# magnetov1.net
KiCad netlist of a schematic drawn in EAGLE
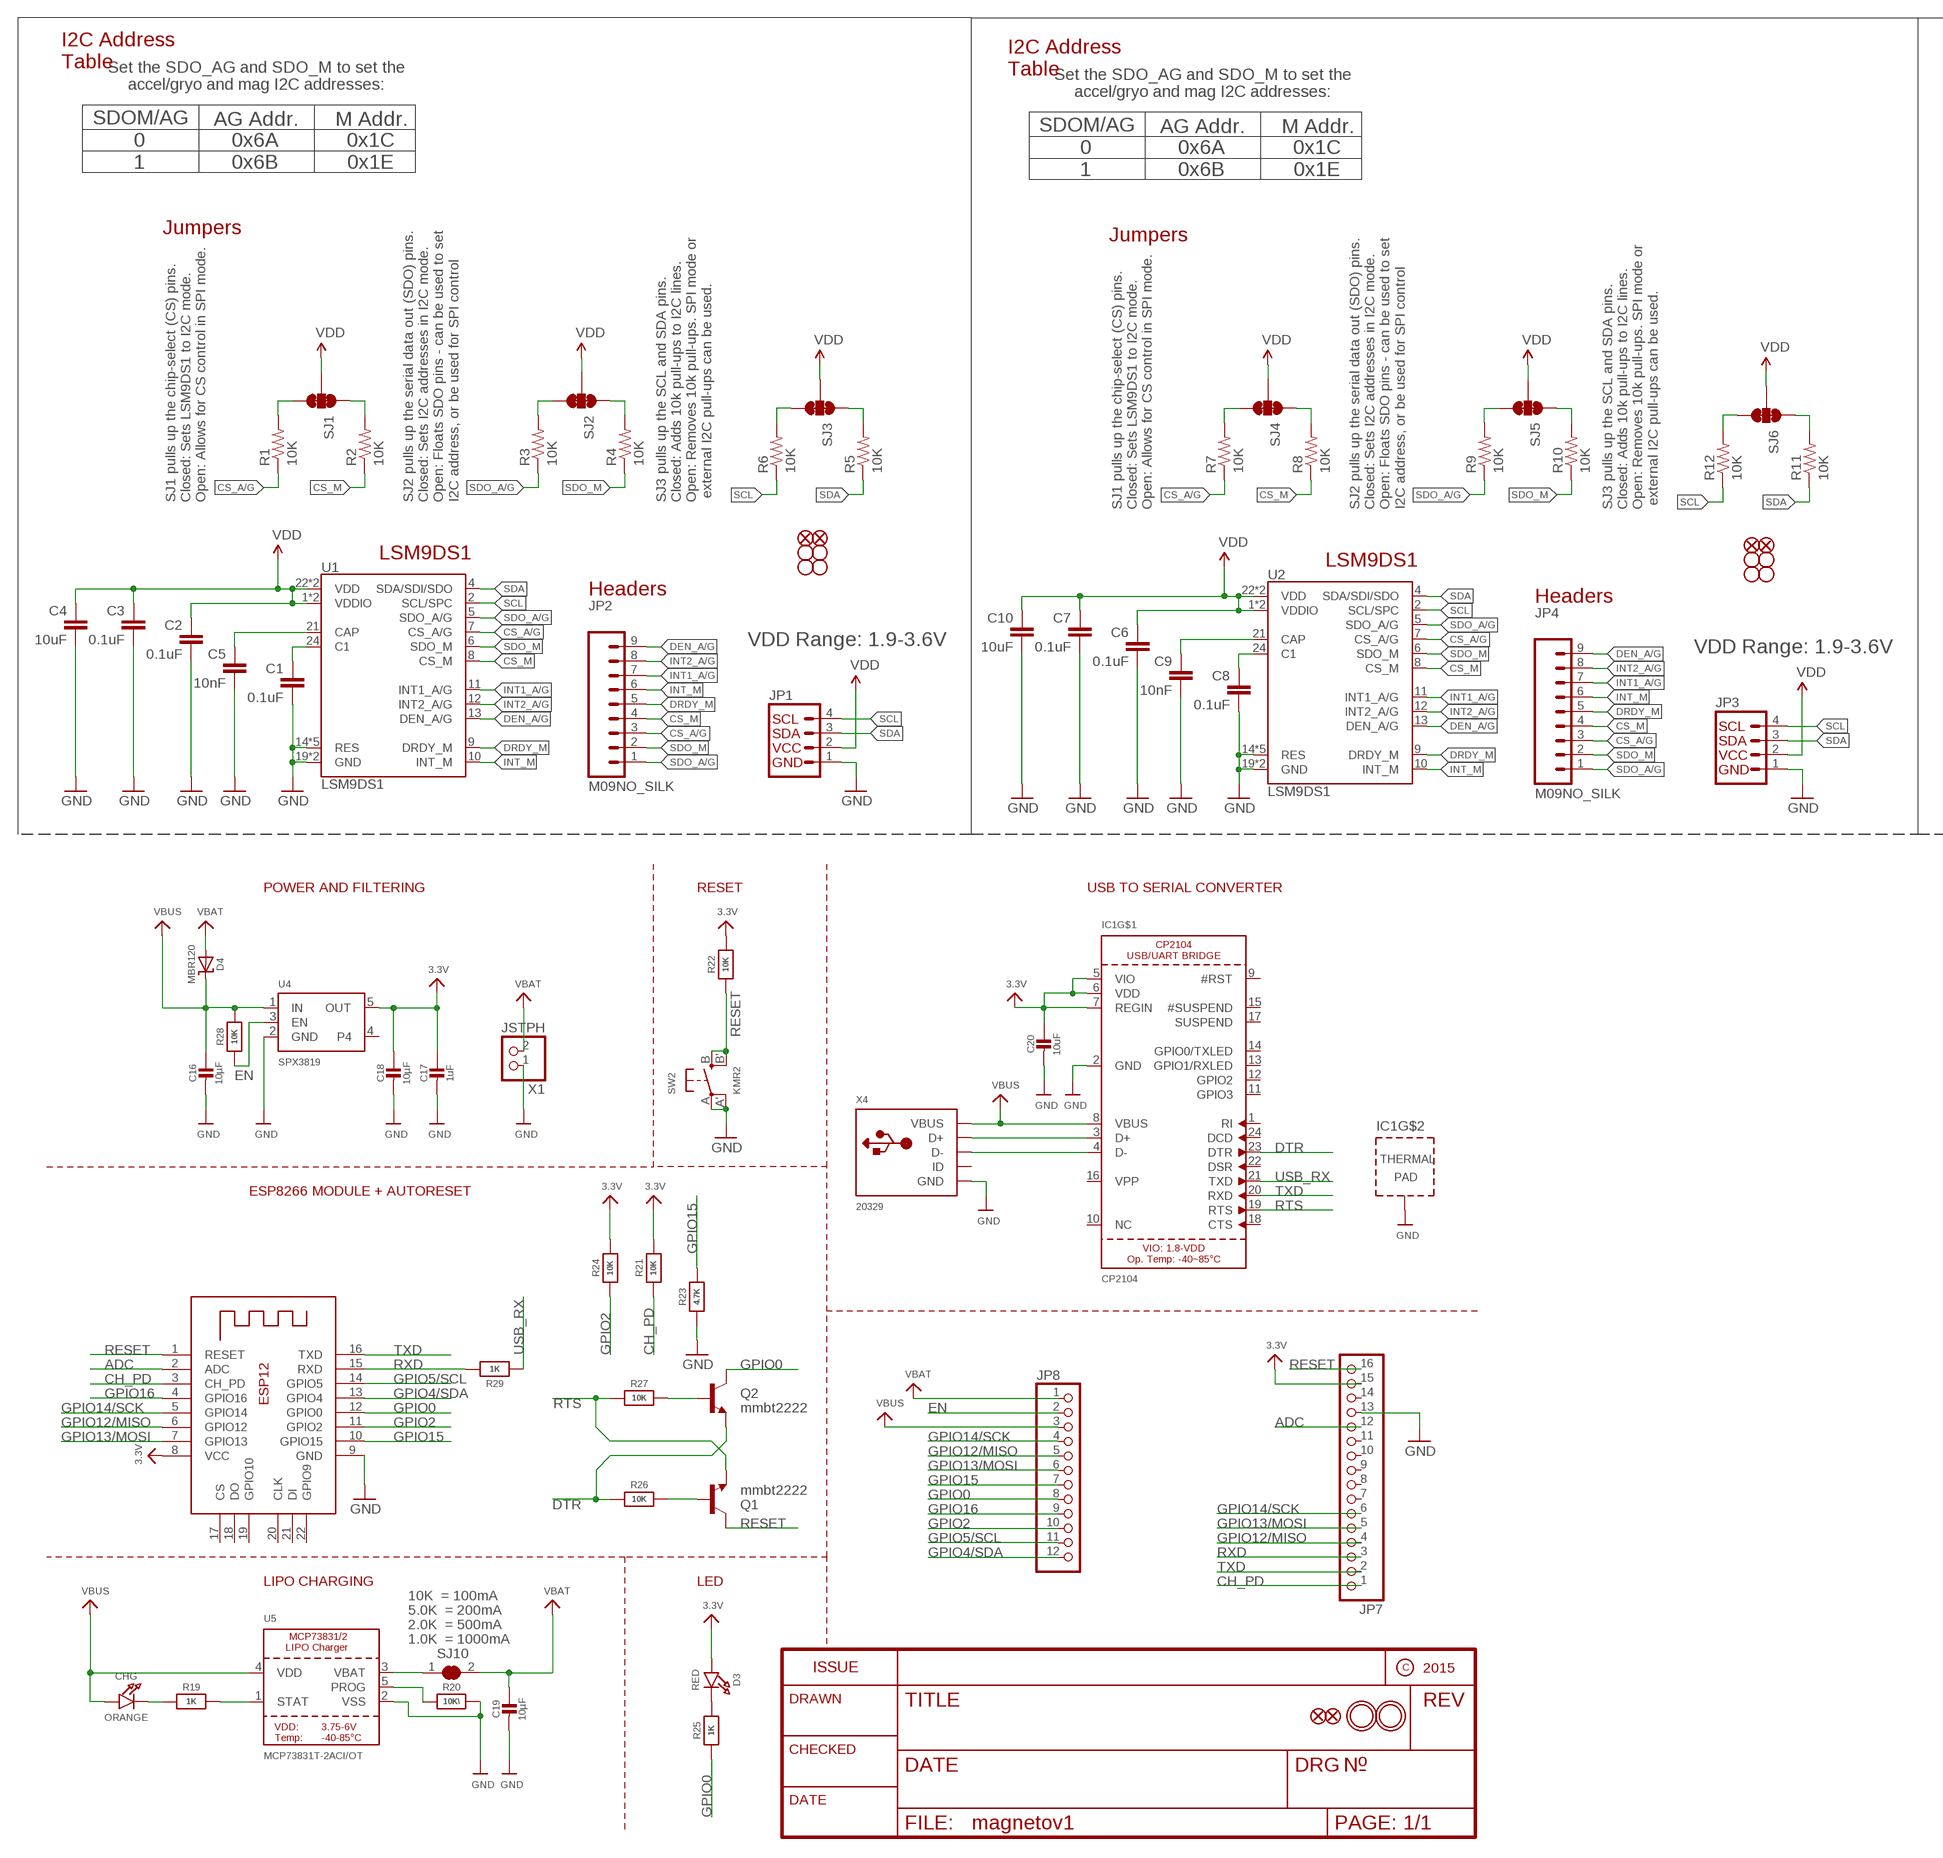
[diagram p0: schematic, sheet 1, part 1 of 2]
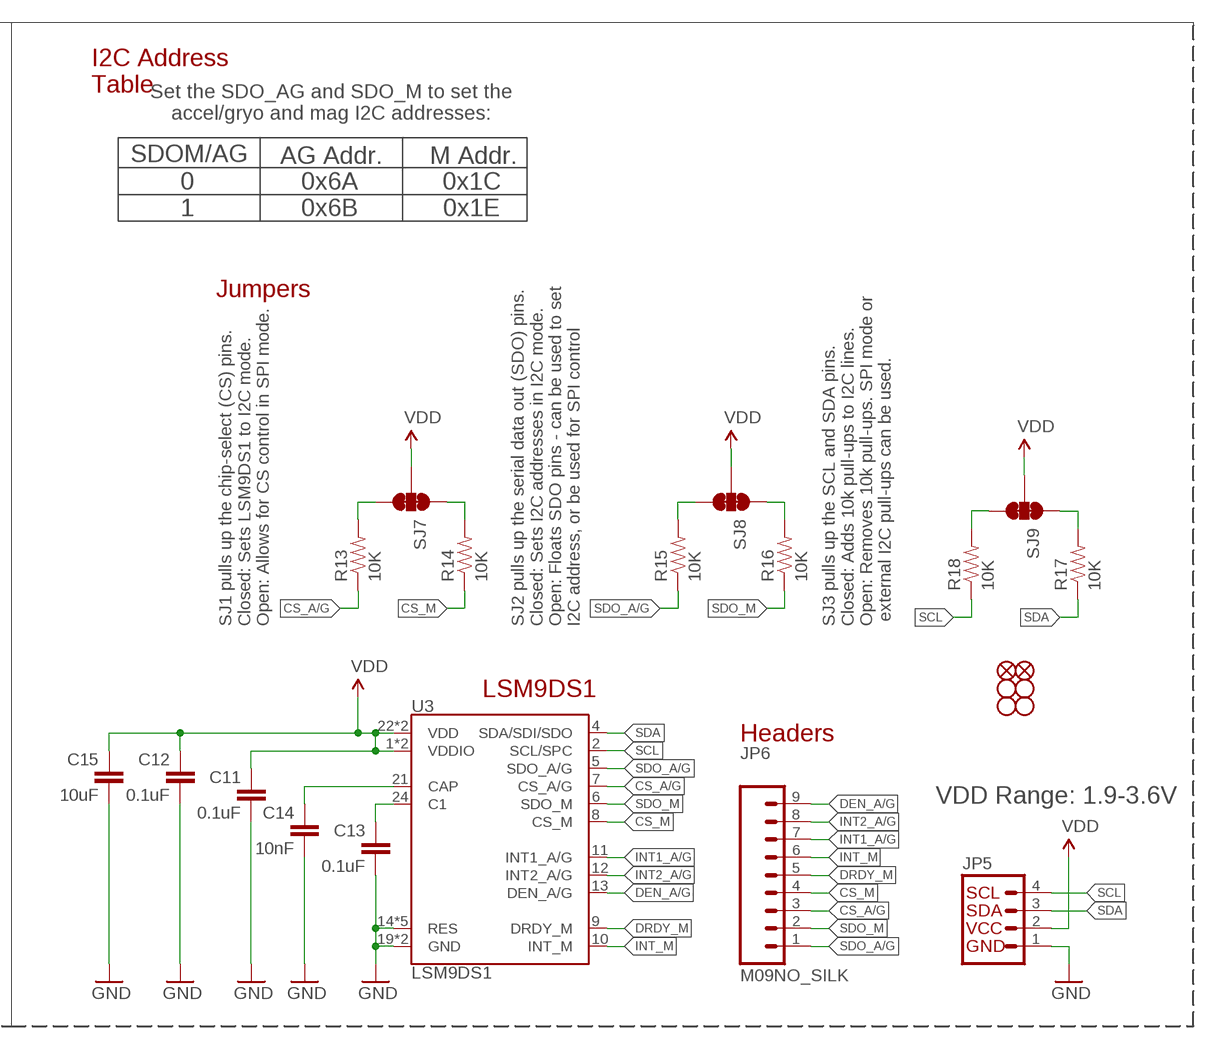
[diagram p1: schematic, sheet 1, part 2 of 2]

(export (version "E")
  (design (tool "Eeschema 10.0.6"))
  (components
    (comp (ref "C1")
      (value "0.1uF")
      (footprint "eagle-import:0603-CAP")
      (libsource (lib "eagle-import") (part "0.1UF-25V(+80/-20%)(0603)"))
    )
    (comp (ref "C2")
      (value "0.1uF")
      (footprint "eagle-import:0603-CAP")
      (libsource (lib "eagle-import") (part "0.1UF-25V(+80/-20%)(0603)"))
    )
    (comp (ref "C3")
      (value "0.1uF")
      (footprint "eagle-import:0603-CAP")
      (libsource (lib "eagle-import") (part "0.1UF-25V(+80/-20%)(0603)"))
    )
    (comp (ref "C4")
      (value "10uF")
      (footprint "eagle-import:0603-CAP")
      (libsource (lib "eagle-import") (part "10UF-6.3V-20%(0603)"))
    )
    (comp (ref "C5")
      (value "10nF")
      (footprint "eagle-import:0603-CAP")
      (libsource (lib "eagle-import") (part "10NF/10000PF-50V-10%(0603)"))
    )
    (comp (ref "C6")
      (value "0.1uF")
      (footprint "eagle-import:0603-CAP")
      (libsource (lib "eagle-import") (part "0.1UF-25V(+80/-20%)(0603)"))
    )
    (comp (ref "C7")
      (value "0.1uF")
      (footprint "eagle-import:0603-CAP")
      (libsource (lib "eagle-import") (part "0.1UF-25V(+80/-20%)(0603)"))
    )
    (comp (ref "C8")
      (value "0.1uF")
      (footprint "eagle-import:0603-CAP")
      (libsource (lib "eagle-import") (part "0.1UF-25V(+80/-20%)(0603)"))
    )
    (comp (ref "C9")
      (value "10nF")
      (footprint "eagle-import:0603-CAP")
      (libsource (lib "eagle-import") (part "10NF/10000PF-50V-10%(0603)"))
    )
    (comp (ref "C10")
      (value "10uF")
      (footprint "eagle-import:0603-CAP")
      (libsource (lib "eagle-import") (part "10UF-6.3V-20%(0603)"))
    )
    (comp (ref "C11")
      (value "0.1uF")
      (footprint "eagle-import:0603-CAP")
      (libsource (lib "eagle-import") (part "0.1UF-25V(+80/-20%)(0603)"))
    )
    (comp (ref "C12")
      (value "0.1uF")
      (footprint "eagle-import:0603-CAP")
      (libsource (lib "eagle-import") (part "0.1UF-25V(+80/-20%)(0603)"))
    )
    (comp (ref "C13")
      (value "0.1uF")
      (footprint "eagle-import:0603-CAP")
      (libsource (lib "eagle-import") (part "0.1UF-25V(+80/-20%)(0603)"))
    )
    (comp (ref "C14")
      (value "10nF")
      (footprint "eagle-import:0603-CAP")
      (libsource (lib "eagle-import") (part "10NF/10000PF-50V-10%(0603)"))
    )
    (comp (ref "C15")
      (value "10uF")
      (footprint "eagle-import:0603-CAP")
      (libsource (lib "eagle-import") (part "10UF-6.3V-20%(0603)"))
    )
    (comp (ref "C16")
      (value "10µF")
      (footprint "eagle-import:0805-NO")
      (libsource (lib "eagle-import") (part "CAP_CERAMIC0805-NOOUTLINE"))
    )
    (comp (ref "C17")
      (value "1uF")
      (footprint "eagle-import:0603-NO")
      (libsource (lib "eagle-import") (part "CAP_CERAMIC0603_NO"))
    )
    (comp (ref "C18")
      (value "10µF")
      (footprint "eagle-import:0805-NO")
      (libsource (lib "eagle-import") (part "CAP_CERAMIC0805-NOOUTLINE"))
    )
    (comp (ref "C19")
      (value "10µF")
      (footprint "eagle-import:0805-NO")
      (libsource (lib "eagle-import") (part "CAP_CERAMIC0805-NOOUTLINE"))
    )
    (comp (ref "C20")
      (value "10uF")
      (footprint "eagle-import:0805-NO")
      (libsource (lib "eagle-import") (part "CAP_CERAMIC0805-NOOUTLINE"))
    )
    (comp (ref "CHG")
      (value "ORANGE")
      (footprint "eagle-import:CHIPLED_0805_NOOUTLINE")
      (libsource (lib "eagle-import") (part "LED0805_NOOUTLINE"))
    )
    (comp (ref "D3")
      (value "RED")
      (footprint "eagle-import:CHIPLED_0805_NOOUTLINE")
      (libsource (lib "eagle-import") (part "LED0805_NOOUTLINE"))
    )
    (comp (ref "D4")
      (value "MBR120")
      (footprint "eagle-import:SOD-123")
      (libsource (lib "eagle-import") (part "DIODE-SCHOTTKYSOD-123"))
    )
    (comp (ref "FID1")
      (value "FIDUCIAL1X2")
      (footprint "eagle-import:FIDUCIAL-1X2")
      (libsource (lib "eagle-import") (part "FIDUCIAL1X2"))
    )
    (comp (ref "FID2")
      (value "FIDUCIAL1X2")
      (footprint "eagle-import:FIDUCIAL-1X2")
      (libsource (lib "eagle-import") (part "FIDUCIAL1X2"))
    )
    (comp (ref "FID3")
      (value "FIDUCIAL1X2")
      (footprint "eagle-import:FIDUCIAL-1X2")
      (libsource (lib "eagle-import") (part "FIDUCIAL1X2"))
    )
    (comp (ref "FID4")
      (value "FIDUCIAL1X2")
      (footprint "eagle-import:FIDUCIAL-1X2")
      (libsource (lib "eagle-import") (part "FIDUCIAL1X2"))
    )
    (comp (ref "FID5")
      (value "FIDUCIAL1X2")
      (footprint "eagle-import:FIDUCIAL-1X2")
      (libsource (lib "eagle-import") (part "FIDUCIAL1X2"))
    )
    (comp (ref "FID6")
      (value "FIDUCIAL1X2")
      (footprint "eagle-import:FIDUCIAL-1X2")
      (libsource (lib "eagle-import") (part "FIDUCIAL1X2"))
    )
    (comp (ref "IC1")
      (value "CP2104")
      (footprint "eagle-import:QFN24_4MM_SMSC")
      (libsource (lib "eagle-import") (part "CP2104"))
    )
    (comp (ref "JP1")
      (value "I2C_STANDARD_NO_SILK")
      (footprint "eagle-import:1X04_NO_SILK")
      (libsource (lib "eagle-import") (part "I2C_STANDARD_NO_SILK"))
    )
    (comp (ref "JP2")
      (value "M09NO_SILK")
      (footprint "eagle-import:1X09_NO_SILK")
      (libsource (lib "eagle-import") (part "M09NO_SILK"))
    )
    (comp (ref "JP3")
      (value "I2C_STANDARD_NO_SILK")
      (footprint "eagle-import:1X04_NO_SILK")
      (libsource (lib "eagle-import") (part "I2C_STANDARD_NO_SILK"))
    )
    (comp (ref "JP4")
      (value "M09NO_SILK")
      (footprint "eagle-import:1X09_NO_SILK")
      (libsource (lib "eagle-import") (part "M09NO_SILK"))
    )
    (comp (ref "JP5")
      (value "I2C_STANDARD_NO_SILK")
      (footprint "eagle-import:1X04_NO_SILK")
      (libsource (lib "eagle-import") (part "I2C_STANDARD_NO_SILK"))
    )
    (comp (ref "JP6")
      (value "M09NO_SILK")
      (footprint "eagle-import:1X09_NO_SILK")
      (libsource (lib "eagle-import") (part "M09NO_SILK"))
    )
    (comp (ref "JP7")
      (value "HEADER-1X16ROUND")
      (footprint "eagle-import:1X16_ROUND")
      (libsource (lib "eagle-import") (part "HEADER-1X16ROUND"))
    )
    (comp (ref "JP8")
      (value "HEADER-1X12")
      (footprint "eagle-import:1X12_ROUND")
      (libsource (lib "eagle-import") (part "HEADER-1X12"))
    )
    (comp (ref "Q1")
      (value "mmbt2222")
      (footprint "eagle-import:SOT23-3")
      (libsource (lib "eagle-import") (part "TRANSISTOR_NPNSOT23-3"))
    )
    (comp (ref "Q2")
      (value "mmbt2222")
      (footprint "eagle-import:SOT23-3")
      (libsource (lib "eagle-import") (part "TRANSISTOR_NPNSOT23-3"))
    )
    (comp (ref "R1")
      (value "10K")
      (footprint "eagle-import:0603-RES")
      (libsource (lib "eagle-import") (part "10KOHM-1/10W-1%(0603)0603"))
    )
    (comp (ref "R2")
      (value "10K")
      (footprint "eagle-import:0603-RES")
      (libsource (lib "eagle-import") (part "10KOHM-1/10W-1%(0603)0603"))
    )
    (comp (ref "R3")
      (value "10K")
      (footprint "eagle-import:0603-RES")
      (libsource (lib "eagle-import") (part "10KOHM-1/10W-1%(0603)0603"))
    )
    (comp (ref "R4")
      (value "10K")
      (footprint "eagle-import:0603-RES")
      (libsource (lib "eagle-import") (part "10KOHM-1/10W-1%(0603)0603"))
    )
    (comp (ref "R5")
      (value "10K")
      (footprint "eagle-import:0603-RES")
      (libsource (lib "eagle-import") (part "10KOHM-1/10W-1%(0603)0603"))
    )
    (comp (ref "R6")
      (value "10K")
      (footprint "eagle-import:0603-RES")
      (libsource (lib "eagle-import") (part "10KOHM-1/10W-1%(0603)0603"))
    )
    (comp (ref "R7")
      (value "10K")
      (footprint "eagle-import:0603-RES")
      (libsource (lib "eagle-import") (part "10KOHM-1/10W-1%(0603)0603"))
    )
    (comp (ref "R8")
      (value "10K")
      (footprint "eagle-import:0603-RES")
      (libsource (lib "eagle-import") (part "10KOHM-1/10W-1%(0603)0603"))
    )
    (comp (ref "R9")
      (value "10K")
      (footprint "eagle-import:0603-RES")
      (libsource (lib "eagle-import") (part "10KOHM-1/10W-1%(0603)0603"))
    )
    (comp (ref "R10")
      (value "10K")
      (footprint "eagle-import:0603-RES")
      (libsource (lib "eagle-import") (part "10KOHM-1/10W-1%(0603)0603"))
    )
    (comp (ref "R11")
      (value "10K")
      (footprint "eagle-import:0603-RES")
      (libsource (lib "eagle-import") (part "10KOHM-1/10W-1%(0603)0603"))
    )
    (comp (ref "R12")
      (value "10K")
      (footprint "eagle-import:0603-RES")
      (libsource (lib "eagle-import") (part "10KOHM-1/10W-1%(0603)0603"))
    )
    (comp (ref "R13")
      (value "10K")
      (footprint "eagle-import:0603-RES")
      (libsource (lib "eagle-import") (part "10KOHM-1/10W-1%(0603)0603"))
    )
    (comp (ref "R14")
      (value "10K")
      (footprint "eagle-import:0603-RES")
      (libsource (lib "eagle-import") (part "10KOHM-1/10W-1%(0603)0603"))
    )
    (comp (ref "R15")
      (value "10K")
      (footprint "eagle-import:0603-RES")
      (libsource (lib "eagle-import") (part "10KOHM-1/10W-1%(0603)0603"))
    )
    (comp (ref "R16")
      (value "10K")
      (footprint "eagle-import:0603-RES")
      (libsource (lib "eagle-import") (part "10KOHM-1/10W-1%(0603)0603"))
    )
    (comp (ref "R17")
      (value "10K")
      (footprint "eagle-import:0603-RES")
      (libsource (lib "eagle-import") (part "10KOHM-1/10W-1%(0603)0603"))
    )
    (comp (ref "R18")
      (value "10K")
      (footprint "eagle-import:0603-RES")
      (libsource (lib "eagle-import") (part "10KOHM-1/10W-1%(0603)0603"))
    )
    (comp (ref "R19")
      (value "1K")
      (footprint "eagle-import:0603-NO")
      (libsource (lib "eagle-import") (part "RESISTOR_0603_NOOUT"))
    )
    (comp (ref "R20")
      (value "10K\\")
      (footprint "eagle-import:0603-NO")
      (libsource (lib "eagle-import") (part "RESISTOR_0603_NOOUT"))
    )
    (comp (ref "R21")
      (value "10K")
      (footprint "eagle-import:0603-NO")
      (libsource (lib "eagle-import") (part "RESISTOR_0603_NOOUT"))
    )
    (comp (ref "R22")
      (value "10K")
      (footprint "eagle-import:0603-NO")
      (libsource (lib "eagle-import") (part "RESISTOR_0603_NOOUT"))
    )
    (comp (ref "R23")
      (value "4.7K")
      (footprint "eagle-import:0603-NO")
      (libsource (lib "eagle-import") (part "RESISTOR_0603_NOOUT"))
    )
    (comp (ref "R24")
      (value "10K")
      (footprint "eagle-import:0603-NO")
      (libsource (lib "eagle-import") (part "RESISTOR_0603_NOOUT"))
    )
    (comp (ref "R25")
      (value "1K")
      (footprint "eagle-import:0603-NO")
      (libsource (lib "eagle-import") (part "RESISTOR_0603_NOOUT"))
    )
    (comp (ref "R26")
      (value "10K")
      (footprint "eagle-import:0603-NO")
      (libsource (lib "eagle-import") (part "RESISTOR_0603_NOOUT"))
    )
    (comp (ref "R27")
      (value "10K")
      (footprint "eagle-import:_0603MP")
      (libsource (lib "eagle-import") (part "RESISTOR_0603MP"))
    )
    (comp (ref "R28")
      (value "10K")
      (footprint "eagle-import:0603-NO")
      (libsource (lib "eagle-import") (part "RESISTOR_0603_NOOUT"))
    )
    (comp (ref "R29")
      (value "1K")
      (footprint "eagle-import:_0603MP")
      (libsource (lib "eagle-import") (part "RESISTOR_0603MP"))
    )
    (comp (ref "SJ1")
      (value "JUMPER-PAD-3-NC_BY_TRACE")
      (footprint "eagle-import:PAD-JUMPER-3-3OF3_NC_BY_TRACE_YES_SILK_FULL_BOX")
      (libsource (lib "eagle-import") (part "JUMPER-PAD-3-NC_BY_TRACE"))
    )
    (comp (ref "SJ2")
      (value "JUMPER-PAD-3-NC_BY_TRACE")
      (footprint "eagle-import:PAD-JUMPER-3-3OF3_NC_BY_TRACE_YES_SILK_FULL_BOX")
      (libsource (lib "eagle-import") (part "JUMPER-PAD-3-NC_BY_TRACE"))
    )
    (comp (ref "SJ3")
      (value "JUMPER-PAD-3-NC_BY_TRACE")
      (footprint "eagle-import:PAD-JUMPER-3-3OF3_NC_BY_TRACE_YES_SILK_FULL_BOX")
      (libsource (lib "eagle-import") (part "JUMPER-PAD-3-NC_BY_TRACE"))
    )
    (comp (ref "SJ4")
      (value "JUMPER-PAD-3-NC_BY_TRACE")
      (footprint "eagle-import:PAD-JUMPER-3-3OF3_NC_BY_TRACE_YES_SILK_FULL_BOX")
      (libsource (lib "eagle-import") (part "JUMPER-PAD-3-NC_BY_TRACE"))
    )
    (comp (ref "SJ5")
      (value "JUMPER-PAD-3-NC_BY_TRACE")
      (footprint "eagle-import:PAD-JUMPER-3-3OF3_NC_BY_TRACE_YES_SILK_FULL_BOX")
      (libsource (lib "eagle-import") (part "JUMPER-PAD-3-NC_BY_TRACE"))
    )
    (comp (ref "SJ6")
      (value "JUMPER-PAD-3-NC_BY_TRACE")
      (footprint "eagle-import:PAD-JUMPER-3-3OF3_NC_BY_TRACE_YES_SILK_FULL_BOX")
      (libsource (lib "eagle-import") (part "JUMPER-PAD-3-NC_BY_TRACE"))
    )
    (comp (ref "SJ7")
      (value "JUMPER-PAD-3-NC_BY_TRACE")
      (footprint "eagle-import:PAD-JUMPER-3-3OF3_NC_BY_TRACE_YES_SILK_FULL_BOX")
      (libsource (lib "eagle-import") (part "JUMPER-PAD-3-NC_BY_TRACE"))
    )
    (comp (ref "SJ8")
      (value "JUMPER-PAD-3-NC_BY_TRACE")
      (footprint "eagle-import:PAD-JUMPER-3-3OF3_NC_BY_TRACE_YES_SILK_FULL_BOX")
      (libsource (lib "eagle-import") (part "JUMPER-PAD-3-NC_BY_TRACE"))
    )
    (comp (ref "SJ9")
      (value "JUMPER-PAD-3-NC_BY_TRACE")
      (footprint "eagle-import:PAD-JUMPER-3-3OF3_NC_BY_TRACE_YES_SILK_FULL_BOX")
      (libsource (lib "eagle-import") (part "JUMPER-PAD-3-NC_BY_TRACE"))
    )
    (comp (ref "SJ10")
      (value "SOLDERJUMPER_CLOSED")
      (footprint "eagle-import:SOLDERJUMPER_CLOSEDWIRE")
      (libsource (lib "eagle-import") (part "SOLDERJUMPER_CLOSED"))
    )
    (comp (ref "STANDOFF1")
      (value "STAND-OFF")
      (footprint "eagle-import:STAND-OFF")
      (libsource (lib "eagle-import") (part "STAND-OFF"))
    )
    (comp (ref "STANDOFF2")
      (value "STAND-OFF")
      (footprint "eagle-import:STAND-OFF")
      (libsource (lib "eagle-import") (part "STAND-OFF"))
    )
    (comp (ref "STANDOFF3")
      (value "STAND-OFF")
      (footprint "eagle-import:STAND-OFF")
      (libsource (lib "eagle-import") (part "STAND-OFF"))
    )
    (comp (ref "STANDOFF4")
      (value "STAND-OFF")
      (footprint "eagle-import:STAND-OFF")
      (libsource (lib "eagle-import") (part "STAND-OFF"))
    )
    (comp (ref "STANDOFF5")
      (value "STAND-OFF")
      (footprint "eagle-import:STAND-OFF")
      (libsource (lib "eagle-import") (part "STAND-OFF"))
    )
    (comp (ref "STANDOFF6")
      (value "STAND-OFF")
      (footprint "eagle-import:STAND-OFF")
      (libsource (lib "eagle-import") (part "STAND-OFF"))
    )
    (comp (ref "STANDOFF7")
      (value "STAND-OFF")
      (footprint "eagle-import:STAND-OFF")
      (libsource (lib "eagle-import") (part "STAND-OFF"))
    )
    (comp (ref "STANDOFF8")
      (value "STAND-OFF")
      (footprint "eagle-import:STAND-OFF")
      (libsource (lib "eagle-import") (part "STAND-OFF"))
    )
    (comp (ref "STANDOFF9")
      (value "STAND-OFF")
      (footprint "eagle-import:STAND-OFF")
      (libsource (lib "eagle-import") (part "STAND-OFF"))
    )
    (comp (ref "STANDOFF10")
      (value "STAND-OFF")
      (footprint "eagle-import:STAND-OFF")
      (libsource (lib "eagle-import") (part "STAND-OFF"))
    )
    (comp (ref "STANDOFF11")
      (value "STAND-OFF")
      (footprint "eagle-import:STAND-OFF")
      (libsource (lib "eagle-import") (part "STAND-OFF"))
    )
    (comp (ref "STANDOFF12")
      (value "STAND-OFF")
      (footprint "eagle-import:STAND-OFF")
      (libsource (lib "eagle-import") (part "STAND-OFF"))
    )
    (comp (ref "SW2")
      (value "KMR2")
      (footprint "eagle-import:BTN_KMR2_4.6X2.8")
      (libsource (lib "eagle-import") (part "SWITCH_TACT_SMT4.6X2.8"))
    )
    (comp (ref "U$31")
      (value "MOUNTINGHOLE2.5")
      (footprint "eagle-import:MOUNTINGHOLE_2.5_PLATED")
      (libsource (lib "eagle-import") (part "MOUNTINGHOLE2.5"))
    )
    (comp (ref "U$32")
      (value "MOUNTINGHOLE2.5")
      (footprint "eagle-import:MOUNTINGHOLE_2.5_PLATED")
      (libsource (lib "eagle-import") (part "MOUNTINGHOLE2.5"))
    )
    (comp (ref "U$34")
      (value "FIDUCIAL\"\"")
      (footprint "eagle-import:FIDUCIAL_1MM")
      (libsource (lib "eagle-import") (part "FIDUCIAL{dblquote}{dblquote}"))
    )
    (comp (ref "U$35")
      (value "FIDUCIAL\"\"")
      (footprint "eagle-import:FIDUCIAL_1MM")
      (libsource (lib "eagle-import") (part "FIDUCIAL{dblquote}{dblquote}"))
    )
    (comp (ref "U1")
      (value "LSM9DS1")
      (footprint "eagle-import:LGA24-8X4")
      (libsource (lib "eagle-import") (part "LSM9DS1"))
    )
    (comp (ref "U2")
      (value "LSM9DS1")
      (footprint "eagle-import:LGA24-8X4")
      (libsource (lib "eagle-import") (part "LSM9DS1"))
    )
    (comp (ref "U3")
      (value "LSM9DS1")
      (footprint "eagle-import:LGA24-8X4")
      (libsource (lib "eagle-import") (part "LSM9DS1"))
    )
    (comp (ref "U4")
      (value "SPX3819")
      (footprint "eagle-import:SOT23-5")
      (libsource (lib "eagle-import") (part "VREG_SOT23-5"))
    )
    (comp (ref "U5")
      (value "MCP73831T-2ACI/OT")
      (footprint "eagle-import:SOT23-5")
      (libsource (lib "eagle-import") (part "MCP73831/2"))
    )
    (comp (ref "X1")
      (value "JSTPH")
      (footprint "eagle-import:JSTPH2")
      (libsource (lib "eagle-import") (part "CON_JST_PH_2PIN"))
    )
    (comp (ref "X2")
      (value "ESP-12")
      (footprint "eagle-import:ESP-12E")
      (libsource (lib "eagle-import") (part "ESP-12E"))
    )
    (comp (ref "X4")
      (value "20329")
      (footprint "eagle-import:4UCONN_20329_V2")
      (libsource (lib "eagle-import") (part "USB_MICRO_20329_V2"))
    )
  )
  (nets
    (net (code "1") (name "/ADC") (class "Default")
      (node (ref "JP7") (pin "12") (pinfunction "12_12") (pintype "passive"))
      (node (ref "X2") (pin "2") (pinfunction "ADC_2") (pintype "passive"))
    )
    (net (code "2") (name "/CH_PD") (class "Default")
      (node (ref "JP7") (pin "1") (pinfunction "1_1") (pintype "passive"))
      (node (ref "R21") (pin "1") (pinfunction "1_1") (pintype "passive"))
      (node (ref "X2") (pin "3") (pinfunction "CH_PD_3") (pintype "input"))
    )
    (net (code "3") (name "/DTR") (class "Default")
      (node (ref "IC1") (pin "23") (pinfunction "DTR_23") (pintype "output"))
      (node (ref "Q2") (pin "2") (pinfunction "E_2") (pintype "passive"))
      (node (ref "R26") (pin "1") (pinfunction "1_1") (pintype "passive"))
    )
    (net (code "4") (name "/EN") (class "Default")
      (node (ref "JP8") (pin "2") (pinfunction "2_2") (pintype "passive"))
      (node (ref "R28") (pin "1") (pinfunction "1_1") (pintype "passive"))
      (node (ref "U4") (pin "3") (pinfunction "EN_3") (pintype "input"))
    )
    (net (code "5") (name "/GPIO0") (class "Default")
      (node (ref "JP8") (pin "8") (pinfunction "8_8") (pintype "passive"))
      (node (ref "Q2") (pin "3") (pinfunction "C_3") (pintype "passive"))
      (node (ref "R25") (pin "1") (pinfunction "1_1") (pintype "passive"))
      (node (ref "X2") (pin "12") (pinfunction "GPIO0_12") (pintype "bidirectional"))
    )
    (net (code "6") (name "/GPIO2") (class "Default")
      (node (ref "JP8") (pin "10") (pinfunction "10_10") (pintype "passive"))
      (node (ref "R24") (pin "1") (pinfunction "1_1") (pintype "passive"))
      (node (ref "X2") (pin "11") (pinfunction "GPIO2_11") (pintype "bidirectional"))
    )
    (net (code "7") (name "/GPIO4{slash}SDA") (class "Default")
      (node (ref "JP8") (pin "12") (pinfunction "12_12") (pintype "passive"))
      (node (ref "X2") (pin "13") (pinfunction "GPIO4_13") (pintype "bidirectional"))
    )
    (net (code "8") (name "/GPIO5{slash}SCL") (class "Default")
      (node (ref "JP8") (pin "11") (pinfunction "11_11") (pintype "passive"))
      (node (ref "X2") (pin "14") (pinfunction "GPIO5_14") (pintype "bidirectional"))
    )
    (net (code "9") (name "/GPIO12{slash}MISO") (class "Default")
      (node (ref "JP7") (pin "4") (pinfunction "4_4") (pintype "passive"))
      (node (ref "JP8") (pin "5") (pinfunction "5_5") (pintype "passive"))
      (node (ref "X2") (pin "6") (pinfunction "GPIO12_6") (pintype "bidirectional"))
    )
    (net (code "10") (name "/GPIO13{slash}MOSI") (class "Default")
      (node (ref "JP7") (pin "5") (pinfunction "5_5") (pintype "passive"))
      (node (ref "JP8") (pin "6") (pinfunction "6_6") (pintype "passive"))
      (node (ref "X2") (pin "7") (pinfunction "GPIO13_7") (pintype "bidirectional"))
    )
    (net (code "11") (name "/GPIO14{slash}SCK") (class "Default")
      (node (ref "JP7") (pin "6") (pinfunction "6_6") (pintype "passive"))
      (node (ref "JP8") (pin "4") (pinfunction "4_4") (pintype "passive"))
      (node (ref "X2") (pin "5") (pinfunction "GPIO14_5") (pintype "bidirectional"))
    )
    (net (code "12") (name "/GPIO15") (class "Default")
      (node (ref "JP8") (pin "7") (pinfunction "7_7") (pintype "passive"))
      (node (ref "R23") (pin "2") (pinfunction "2_2") (pintype "passive"))
      (node (ref "X2") (pin "10") (pinfunction "GPIO15_10") (pintype "bidirectional"))
    )
    (net (code "13") (name "/GPIO16") (class "Default")
      (node (ref "JP8") (pin "9") (pinfunction "9_9") (pintype "passive"))
      (node (ref "X2") (pin "4") (pinfunction "GPIO16_4") (pintype "bidirectional"))
    )
    (net (code "14") (name "/RESET") (class "Default")
      (node (ref "JP7") (pin "16") (pinfunction "16_16") (pintype "passive"))
      (node (ref "Q1") (pin "3") (pinfunction "C_3") (pintype "passive"))
      (node (ref "R22") (pin "1") (pinfunction "1_1") (pintype "passive"))
      (node (ref "SW2") (pin "B") (pinfunction "S_B") (pintype "passive"))
      (node (ref "SW2") (pin "B'") (pinfunction "S1_B'") (pintype "passive"))
      (node (ref "X2") (pin "1") (pinfunction "RESET_1") (pintype "input"))
    )
    (net (code "15") (name "/RTS") (class "Default")
      (node (ref "IC1") (pin "19") (pinfunction "RTS_19") (pintype "output"))
      (node (ref "Q1") (pin "2") (pinfunction "E_2") (pintype "passive"))
      (node (ref "R27") (pin "1") (pinfunction "1_1") (pintype "passive"))
    )
    (net (code "16") (name "/RXD") (class "Default")
      (node (ref "JP7") (pin "3") (pinfunction "3_3") (pintype "passive"))
      (node (ref "R29") (pin "2") (pinfunction "2_2") (pintype "passive"))
      (node (ref "X2") (pin "15") (pinfunction "RXD_15") (pintype "input"))
    )
    (net (code "17") (name "/TXD") (class "Default")
      (node (ref "IC1") (pin "20") (pinfunction "RXD_20") (pintype "input"))
      (node (ref "JP7") (pin "2") (pinfunction "2_2") (pintype "passive"))
      (node (ref "X2") (pin "16") (pinfunction "TXD_16") (pintype "output"))
    )
    (net (code "18") (name "/USB_RX") (class "Default")
      (node (ref "IC1") (pin "21") (pinfunction "TXD_21") (pintype "output"))
      (node (ref "R29") (pin "1") (pinfunction "1_1") (pintype "passive"))
    )
    (net (code "19") (name "3.3V") (class "Default")
      (node (ref "C17") (pin "1") (pinfunction "1_1") (pintype "passive"))
      (node (ref "C18") (pin "1") (pinfunction "1_1") (pintype "passive"))
      (node (ref "C20") (pin "1") (pinfunction "1_1") (pintype "passive"))
      (node (ref "D3") (pin "A") (pinfunction "A_A") (pintype "passive"))
      (node (ref "IC1") (pin "5") (pinfunction "VIO_5") (pintype "power_in"))
      (node (ref "IC1") (pin "6") (pinfunction "VDD_6") (pintype "power_in"))
      (node (ref "IC1") (pin "7") (pinfunction "REGIN_7") (pintype "power_in"))
      (node (ref "JP7") (pin "15") (pinfunction "15_15") (pintype "passive"))
      (node (ref "R21") (pin "2") (pinfunction "2_2") (pintype "passive"))
      (node (ref "R22") (pin "2") (pinfunction "2_2") (pintype "passive"))
      (node (ref "R24") (pin "2") (pinfunction "2_2") (pintype "passive"))
      (node (ref "U4") (pin "5") (pinfunction "OUT_5") (pintype "power_in"))
      (node (ref "X2") (pin "8") (pinfunction "VCC_8") (pintype "power_in"))
    )
    (net (code "20") (name "CS_A{slash}G") (class "Default")
      (node (ref "JP2") (pin "3") (pinfunction "3_3") (pintype "passive"))
      (node (ref "JP4") (pin "3") (pinfunction "3_3") (pintype "passive"))
      (node (ref "JP6") (pin "3") (pinfunction "3_3") (pintype "passive"))
      (node (ref "R1") (pin "1") (pinfunction "1_1") (pintype "passive"))
      (node (ref "R13") (pin "1") (pinfunction "1_1") (pintype "passive"))
      (node (ref "R7") (pin "1") (pinfunction "1_1") (pintype "passive"))
      (node (ref "U1") (pin "7") (pinfunction "CS_A/G_7") (pintype "bidirectional"))
      (node (ref "U2") (pin "7") (pinfunction "CS_A/G_7") (pintype "bidirectional"))
      (node (ref "U3") (pin "7") (pinfunction "CS_A/G_7") (pintype "bidirectional"))
    )
    (net (code "21") (name "CS_M") (class "Default")
      (node (ref "JP2") (pin "4") (pinfunction "4_4") (pintype "passive"))
      (node (ref "JP4") (pin "4") (pinfunction "4_4") (pintype "passive"))
      (node (ref "JP6") (pin "4") (pinfunction "4_4") (pintype "passive"))
      (node (ref "R14") (pin "1") (pinfunction "1_1") (pintype "passive"))
      (node (ref "R2") (pin "1") (pinfunction "1_1") (pintype "passive"))
      (node (ref "R8") (pin "1") (pinfunction "1_1") (pintype "passive"))
      (node (ref "U1") (pin "8") (pinfunction "CS_M_8") (pintype "bidirectional"))
      (node (ref "U2") (pin "8") (pinfunction "CS_M_8") (pintype "bidirectional"))
      (node (ref "U3") (pin "8") (pinfunction "CS_M_8") (pintype "bidirectional"))
    )
    (net (code "22") (name "DEN_A{slash}G") (class "Default")
      (node (ref "JP2") (pin "9") (pinfunction "9_9") (pintype "passive"))
      (node (ref "JP4") (pin "9") (pinfunction "9_9") (pintype "passive"))
      (node (ref "JP6") (pin "9") (pinfunction "9_9") (pintype "passive"))
      (node (ref "U1") (pin "13") (pinfunction "DEN_A/G_13") (pintype "bidirectional"))
      (node (ref "U2") (pin "13") (pinfunction "DEN_A/G_13") (pintype "bidirectional"))
      (node (ref "U3") (pin "13") (pinfunction "DEN_A/G_13") (pintype "bidirectional"))
    )
    (net (code "23") (name "DRDY_M") (class "Default")
      (node (ref "JP2") (pin "5") (pinfunction "5_5") (pintype "passive"))
      (node (ref "JP4") (pin "5") (pinfunction "5_5") (pintype "passive"))
      (node (ref "JP6") (pin "5") (pinfunction "5_5") (pintype "passive"))
      (node (ref "U1") (pin "9") (pinfunction "DRDY_M_9") (pintype "bidirectional"))
      (node (ref "U2") (pin "9") (pinfunction "DRDY_M_9") (pintype "bidirectional"))
      (node (ref "U3") (pin "9") (pinfunction "DRDY_M_9") (pintype "bidirectional"))
    )
    (net (code "24") (name "GND") (class "Default")
      (node (ref "C1") (pin "2") (pinfunction "2_2") (pintype "passive"))
      (node (ref "C10") (pin "2") (pinfunction "2_2") (pintype "passive"))
      (node (ref "C11") (pin "2") (pinfunction "2_2") (pintype "passive"))
      (node (ref "C12") (pin "2") (pinfunction "2_2") (pintype "passive"))
      (node (ref "C13") (pin "2") (pinfunction "2_2") (pintype "passive"))
      (node (ref "C14") (pin "2") (pinfunction "2_2") (pintype "passive"))
      (node (ref "C15") (pin "2") (pinfunction "2_2") (pintype "passive"))
      (node (ref "C16") (pin "2") (pinfunction "2_2") (pintype "passive"))
      (node (ref "C17") (pin "2") (pinfunction "2_2") (pintype "passive"))
      (node (ref "C18") (pin "2") (pinfunction "2_2") (pintype "passive"))
      (node (ref "C19") (pin "2") (pinfunction "2_2") (pintype "passive"))
      (node (ref "C2") (pin "2") (pinfunction "2_2") (pintype "passive"))
      (node (ref "C20") (pin "2") (pinfunction "2_2") (pintype "passive"))
      (node (ref "C3") (pin "2") (pinfunction "2_2") (pintype "passive"))
      (node (ref "C4") (pin "2") (pinfunction "2_2") (pintype "passive"))
      (node (ref "C5") (pin "2") (pinfunction "2_2") (pintype "passive"))
      (node (ref "C6") (pin "2") (pinfunction "2_2") (pintype "passive"))
      (node (ref "C7") (pin "2") (pinfunction "2_2") (pintype "passive"))
      (node (ref "C8") (pin "2") (pinfunction "2_2") (pintype "passive"))
      (node (ref "C9") (pin "2") (pinfunction "2_2") (pintype "passive"))
      (node (ref "IC1") (pin "2") (pinfunction "GND_2") (pintype "power_in"))
      (node (ref "IC1") (pin "THERM") (pinfunction "TP_THERM") (pintype "power_in"))
      (node (ref "JP1") (pin "1") (pinfunction "1_1") (pintype "passive"))
      (node (ref "JP3") (pin "1") (pinfunction "1_1") (pintype "passive"))
      (node (ref "JP5") (pin "1") (pinfunction "1_1") (pintype "passive"))
      (node (ref "JP7") (pin "13") (pinfunction "13_13") (pintype "passive"))
      (node (ref "R20") (pin "2") (pinfunction "2_2") (pintype "passive"))
      (node (ref "R23") (pin "1") (pinfunction "1_1") (pintype "passive"))
      (node (ref "SW2") (pin "A") (pinfunction "P_A") (pintype "passive"))
      (node (ref "SW2") (pin "A'") (pinfunction "P1_A'") (pintype "passive"))
      (node (ref "U1") (pin "14") (pinfunction "RES_14") (pintype "bidirectional"))
      (node (ref "U1") (pin "15") (pinfunction "RES_15") (pintype "bidirectional"))
      (node (ref "U1") (pin "16") (pinfunction "RES_16") (pintype "bidirectional"))
      (node (ref "U1") (pin "17") (pinfunction "RES_17") (pintype "bidirectional"))
      (node (ref "U1") (pin "18") (pinfunction "RES_18") (pintype "bidirectional"))
      (node (ref "U1") (pin "19") (pinfunction "GND_19") (pintype "bidirectional"))
      (node (ref "U1") (pin "20") (pinfunction "GND_20") (pintype "bidirectional"))
      (node (ref "U2") (pin "14") (pinfunction "RES_14") (pintype "bidirectional"))
      (node (ref "U2") (pin "15") (pinfunction "RES_15") (pintype "bidirectional"))
      (node (ref "U2") (pin "16") (pinfunction "RES_16") (pintype "bidirectional"))
      (node (ref "U2") (pin "17") (pinfunction "RES_17") (pintype "bidirectional"))
      (node (ref "U2") (pin "18") (pinfunction "RES_18") (pintype "bidirectional"))
      (node (ref "U2") (pin "19") (pinfunction "GND_19") (pintype "bidirectional"))
      (node (ref "U2") (pin "20") (pinfunction "GND_20") (pintype "bidirectional"))
      (node (ref "U3") (pin "14") (pinfunction "RES_14") (pintype "bidirectional"))
      (node (ref "U3") (pin "15") (pinfunction "RES_15") (pintype "bidirectional"))
      (node (ref "U3") (pin "16") (pinfunction "RES_16") (pintype "bidirectional"))
      (node (ref "U3") (pin "17") (pinfunction "RES_17") (pintype "bidirectional"))
      (node (ref "U3") (pin "18") (pinfunction "RES_18") (pintype "bidirectional"))
      (node (ref "U3") (pin "19") (pinfunction "GND_19") (pintype "bidirectional"))
      (node (ref "U3") (pin "20") (pinfunction "GND_20") (pintype "bidirectional"))
      (node (ref "U4") (pin "2") (pinfunction "GND_2") (pintype "power_in"))
      (node (ref "U5") (pin "2") (pinfunction "VSS_2") (pintype "power_in"))
      (node (ref "X1") (pin "1") (pinfunction "1_1") (pintype "passive"))
      (node (ref "X2") (pin "9") (pinfunction "GND_9") (pintype "power_in"))
      (node (ref "X4") (pin "BASE@1") (pinfunction "GND_BASE@1") (pintype "power_in"))
      (node (ref "X4") (pin "BASE@2") (pinfunction "GND_BASE@2") (pintype "power_in"))
      (node (ref "X4") (pin "GND") (pinfunction "GND_GND") (pintype "power_in"))
      (node (ref "X4") (pin "SPRT@1") (pinfunction "GND_SPRT@1") (pintype "power_in"))
      (node (ref "X4") (pin "SPRT@2") (pinfunction "GND_SPRT@2") (pintype "power_in"))
      (node (ref "X4") (pin "SPRT@3") (pinfunction "GND_SPRT@3") (pintype "power_in"))
      (node (ref "X4") (pin "SPRT@4") (pinfunction "GND_SPRT@4") (pintype "power_in"))
    )
    (net (code "25") (name "INT1_A{slash}G") (class "Default")
      (node (ref "JP2") (pin "7") (pinfunction "7_7") (pintype "passive"))
      (node (ref "JP4") (pin "7") (pinfunction "7_7") (pintype "passive"))
      (node (ref "JP6") (pin "7") (pinfunction "7_7") (pintype "passive"))
      (node (ref "U1") (pin "11") (pinfunction "INT1_A/G_11") (pintype "bidirectional"))
      (node (ref "U2") (pin "11") (pinfunction "INT1_A/G_11") (pintype "bidirectional"))
      (node (ref "U3") (pin "11") (pinfunction "INT1_A/G_11") (pintype "bidirectional"))
    )
    (net (code "26") (name "INT2_A{slash}G") (class "Default")
      (node (ref "JP2") (pin "8") (pinfunction "8_8") (pintype "passive"))
      (node (ref "JP4") (pin "8") (pinfunction "8_8") (pintype "passive"))
      (node (ref "JP6") (pin "8") (pinfunction "8_8") (pintype "passive"))
      (node (ref "U1") (pin "12") (pinfunction "INT2_A/G_12") (pintype "bidirectional"))
      (node (ref "U2") (pin "12") (pinfunction "INT2_A/G_12") (pintype "bidirectional"))
      (node (ref "U3") (pin "12") (pinfunction "INT2_A/G_12") (pintype "bidirectional"))
    )
    (net (code "27") (name "INT_M") (class "Default")
      (node (ref "JP2") (pin "6") (pinfunction "6_6") (pintype "passive"))
      (node (ref "JP4") (pin "6") (pinfunction "6_6") (pintype "passive"))
      (node (ref "JP6") (pin "6") (pinfunction "6_6") (pintype "passive"))
      (node (ref "U1") (pin "10") (pinfunction "INT_M_10") (pintype "bidirectional"))
      (node (ref "U2") (pin "10") (pinfunction "INT_M_10") (pintype "bidirectional"))
      (node (ref "U3") (pin "10") (pinfunction "INT_M_10") (pintype "bidirectional"))
    )
    (net (code "28") (name "Net-(CHG-PadC)") (class "Default")
      (node (ref "CHG") (pin "C") (pinfunction "C_C") (pintype "passive"))
      (node (ref "R19") (pin "1") (pinfunction "1_1") (pintype "passive"))
    )
    (net (code "29") (name "Net-(D3-PadC)") (class "Default")
      (node (ref "D3") (pin "C") (pinfunction "C_C") (pintype "passive"))
      (node (ref "R25") (pin "2") (pinfunction "2_2") (pintype "passive"))
    )
    (net (code "30") (name "Net-(IC1A-D+)") (class "Default")
      (node (ref "IC1") (pin "3") (pinfunction "D+_3") (pintype "bidirectional"))
      (node (ref "X4") (pin "D+") (pinfunction "D+_D+") (pintype "bidirectional"))
    )
    (net (code "31") (name "Net-(IC1A-D-)") (class "Default")
      (node (ref "IC1") (pin "4") (pinfunction "D-_4") (pintype "bidirectional"))
      (node (ref "X4") (pin "D-") (pinfunction "D-_D-") (pintype "bidirectional"))
    )
    (net (code "32") (name "Net-(Q1-B)") (class "Default")
      (node (ref "Q1") (pin "1") (pinfunction "B_1") (pintype "passive"))
      (node (ref "R26") (pin "2") (pinfunction "2_2") (pintype "passive"))
    )
    (net (code "33") (name "Net-(Q2-B)") (class "Default")
      (node (ref "Q2") (pin "1") (pinfunction "B_1") (pintype "passive"))
      (node (ref "R27") (pin "2") (pinfunction "2_2") (pintype "passive"))
    )
    (net (code "34") (name "Net-(R1-Pad2)") (class "Default")
      (node (ref "R1") (pin "2") (pinfunction "2_2") (pintype "passive"))
      (node (ref "SJ1") (pin "3") (pinfunction "3_3") (pintype "passive"))
    )
    (net (code "35") (name "Net-(R2-Pad2)") (class "Default")
      (node (ref "R2") (pin "2") (pinfunction "2_2") (pintype "passive"))
      (node (ref "SJ1") (pin "1") (pinfunction "1_1") (pintype "passive"))
    )
    (net (code "36") (name "Net-(R3-Pad2)") (class "Default")
      (node (ref "R3") (pin "2") (pinfunction "2_2") (pintype "passive"))
      (node (ref "SJ2") (pin "3") (pinfunction "3_3") (pintype "passive"))
    )
    (net (code "37") (name "Net-(R4-Pad2)") (class "Default")
      (node (ref "R4") (pin "2") (pinfunction "2_2") (pintype "passive"))
      (node (ref "SJ2") (pin "1") (pinfunction "1_1") (pintype "passive"))
    )
    (net (code "38") (name "Net-(R5-Pad2)") (class "Default")
      (node (ref "R5") (pin "2") (pinfunction "2_2") (pintype "passive"))
      (node (ref "SJ3") (pin "1") (pinfunction "1_1") (pintype "passive"))
    )
    (net (code "39") (name "Net-(R6-Pad2)") (class "Default")
      (node (ref "R6") (pin "2") (pinfunction "2_2") (pintype "passive"))
      (node (ref "SJ3") (pin "3") (pinfunction "3_3") (pintype "passive"))
    )
    (net (code "40") (name "Net-(R7-Pad2)") (class "Default")
      (node (ref "R7") (pin "2") (pinfunction "2_2") (pintype "passive"))
      (node (ref "SJ4") (pin "3") (pinfunction "3_3") (pintype "passive"))
    )
    (net (code "41") (name "Net-(R8-Pad2)") (class "Default")
      (node (ref "R8") (pin "2") (pinfunction "2_2") (pintype "passive"))
      (node (ref "SJ4") (pin "1") (pinfunction "1_1") (pintype "passive"))
    )
    (net (code "42") (name "Net-(R9-Pad2)") (class "Default")
      (node (ref "R9") (pin "2") (pinfunction "2_2") (pintype "passive"))
      (node (ref "SJ5") (pin "3") (pinfunction "3_3") (pintype "passive"))
    )
    (net (code "43") (name "Net-(R10-Pad2)") (class "Default")
      (node (ref "R10") (pin "2") (pinfunction "2_2") (pintype "passive"))
      (node (ref "SJ5") (pin "1") (pinfunction "1_1") (pintype "passive"))
    )
    (net (code "44") (name "Net-(R11-Pad2)") (class "Default")
      (node (ref "R11") (pin "2") (pinfunction "2_2") (pintype "passive"))
      (node (ref "SJ6") (pin "1") (pinfunction "1_1") (pintype "passive"))
    )
    (net (code "45") (name "Net-(R12-Pad2)") (class "Default")
      (node (ref "R12") (pin "2") (pinfunction "2_2") (pintype "passive"))
      (node (ref "SJ6") (pin "3") (pinfunction "3_3") (pintype "passive"))
    )
    (net (code "46") (name "Net-(R13-Pad2)") (class "Default")
      (node (ref "R13") (pin "2") (pinfunction "2_2") (pintype "passive"))
      (node (ref "SJ7") (pin "3") (pinfunction "3_3") (pintype "passive"))
    )
    (net (code "47") (name "Net-(R14-Pad2)") (class "Default")
      (node (ref "R14") (pin "2") (pinfunction "2_2") (pintype "passive"))
      (node (ref "SJ7") (pin "1") (pinfunction "1_1") (pintype "passive"))
    )
    (net (code "48") (name "Net-(R15-Pad2)") (class "Default")
      (node (ref "R15") (pin "2") (pinfunction "2_2") (pintype "passive"))
      (node (ref "SJ8") (pin "3") (pinfunction "3_3") (pintype "passive"))
    )
    (net (code "49") (name "Net-(R16-Pad2)") (class "Default")
      (node (ref "R16") (pin "2") (pinfunction "2_2") (pintype "passive"))
      (node (ref "SJ8") (pin "1") (pinfunction "1_1") (pintype "passive"))
    )
    (net (code "50") (name "Net-(R17-Pad2)") (class "Default")
      (node (ref "R17") (pin "2") (pinfunction "2_2") (pintype "passive"))
      (node (ref "SJ9") (pin "1") (pinfunction "1_1") (pintype "passive"))
    )
    (net (code "51") (name "Net-(R18-Pad2)") (class "Default")
      (node (ref "R18") (pin "2") (pinfunction "2_2") (pintype "passive"))
      (node (ref "SJ9") (pin "3") (pinfunction "3_3") (pintype "passive"))
    )
    (net (code "52") (name "Net-(U1-C1)") (class "Default")
      (node (ref "C1") (pin "1") (pinfunction "1_1") (pintype "passive"))
      (node (ref "U1") (pin "24") (pinfunction "C1_24") (pintype "bidirectional"))
    )
    (net (code "53") (name "Net-(U1-CAP)") (class "Default")
      (node (ref "C5") (pin "1") (pinfunction "1_1") (pintype "passive"))
      (node (ref "U1") (pin "21") (pinfunction "CAP_21") (pintype "bidirectional"))
    )
    (net (code "54") (name "Net-(U2-C1)") (class "Default")
      (node (ref "C8") (pin "1") (pinfunction "1_1") (pintype "passive"))
      (node (ref "U2") (pin "24") (pinfunction "C1_24") (pintype "bidirectional"))
    )
    (net (code "55") (name "Net-(U2-CAP)") (class "Default")
      (node (ref "C9") (pin "1") (pinfunction "1_1") (pintype "passive"))
      (node (ref "U2") (pin "21") (pinfunction "CAP_21") (pintype "bidirectional"))
    )
    (net (code "56") (name "Net-(U3-C1)") (class "Default")
      (node (ref "C13") (pin "1") (pinfunction "1_1") (pintype "passive"))
      (node (ref "U3") (pin "24") (pinfunction "C1_24") (pintype "bidirectional"))
    )
    (net (code "57") (name "Net-(U3-CAP)") (class "Default")
      (node (ref "C14") (pin "1") (pinfunction "1_1") (pintype "passive"))
      (node (ref "U3") (pin "21") (pinfunction "CAP_21") (pintype "bidirectional"))
    )
    (net (code "58") (name "Net-(U5-PROG)") (class "Default")
      (node (ref "R20") (pin "1") (pinfunction "1_1") (pintype "passive"))
      (node (ref "U5") (pin "5") (pinfunction "PROG_5") (pintype "input"))
    )
    (net (code "59") (name "Net-(U5-STAT)") (class "Default")
      (node (ref "R19") (pin "2") (pinfunction "2_2") (pintype "passive"))
      (node (ref "U5") (pin "1") (pinfunction "STAT_1") (pintype "output"))
    )
    (net (code "60") (name "Net-(U5-VBAT)") (class "Default")
      (node (ref "SJ10") (pin "1") (pinfunction "1_1") (pintype "passive"))
      (node (ref "U5") (pin "3") (pinfunction "VBAT_3") (pintype "power_in"))
    )
    (net (code "61") (name "SCL") (class "Default")
      (node (ref "JP1") (pin "4") (pinfunction "4_4") (pintype "passive"))
      (node (ref "JP3") (pin "4") (pinfunction "4_4") (pintype "passive"))
      (node (ref "JP5") (pin "4") (pinfunction "4_4") (pintype "passive"))
      (node (ref "R12") (pin "1") (pinfunction "1_1") (pintype "passive"))
      (node (ref "R18") (pin "1") (pinfunction "1_1") (pintype "passive"))
      (node (ref "R6") (pin "1") (pinfunction "1_1") (pintype "passive"))
      (node (ref "U1") (pin "2") (pinfunction "SCL/SPC_2") (pintype "bidirectional"))
      (node (ref "U2") (pin "2") (pinfunction "SCL/SPC_2") (pintype "bidirectional"))
      (node (ref "U3") (pin "2") (pinfunction "SCL/SPC_2") (pintype "bidirectional"))
    )
    (net (code "62") (name "SDA") (class "Default")
      (node (ref "JP1") (pin "3") (pinfunction "3_3") (pintype "passive"))
      (node (ref "JP3") (pin "3") (pinfunction "3_3") (pintype "passive"))
      (node (ref "JP5") (pin "3") (pinfunction "3_3") (pintype "passive"))
      (node (ref "R11") (pin "1") (pinfunction "1_1") (pintype "passive"))
      (node (ref "R17") (pin "1") (pinfunction "1_1") (pintype "passive"))
      (node (ref "R5") (pin "1") (pinfunction "1_1") (pintype "passive"))
      (node (ref "U1") (pin "4") (pinfunction "SDA/SDI/SDO_4") (pintype "bidirectional"))
      (node (ref "U2") (pin "4") (pinfunction "SDA/SDI/SDO_4") (pintype "bidirectional"))
      (node (ref "U3") (pin "4") (pinfunction "SDA/SDI/SDO_4") (pintype "bidirectional"))
    )
    (net (code "63") (name "SDO_A{slash}G") (class "Default")
      (node (ref "JP2") (pin "1") (pinfunction "1_1") (pintype "passive"))
      (node (ref "JP4") (pin "1") (pinfunction "1_1") (pintype "passive"))
      (node (ref "JP6") (pin "1") (pinfunction "1_1") (pintype "passive"))
      (node (ref "R15") (pin "1") (pinfunction "1_1") (pintype "passive"))
      (node (ref "R3") (pin "1") (pinfunction "1_1") (pintype "passive"))
      (node (ref "R9") (pin "1") (pinfunction "1_1") (pintype "passive"))
      (node (ref "U1") (pin "5") (pinfunction "SDO_A/G_5") (pintype "bidirectional"))
      (node (ref "U2") (pin "5") (pinfunction "SDO_A/G_5") (pintype "bidirectional"))
      (node (ref "U3") (pin "5") (pinfunction "SDO_A/G_5") (pintype "bidirectional"))
    )
    (net (code "64") (name "SDO_M") (class "Default")
      (node (ref "JP2") (pin "2") (pinfunction "2_2") (pintype "passive"))
      (node (ref "JP4") (pin "2") (pinfunction "2_2") (pintype "passive"))
      (node (ref "JP6") (pin "2") (pinfunction "2_2") (pintype "passive"))
      (node (ref "R10") (pin "1") (pinfunction "1_1") (pintype "passive"))
      (node (ref "R16") (pin "1") (pinfunction "1_1") (pintype "passive"))
      (node (ref "R4") (pin "1") (pinfunction "1_1") (pintype "passive"))
      (node (ref "U1") (pin "6") (pinfunction "SDO_M_6") (pintype "bidirectional"))
      (node (ref "U2") (pin "6") (pinfunction "SDO_M_6") (pintype "bidirectional"))
      (node (ref "U3") (pin "6") (pinfunction "SDO_M_6") (pintype "bidirectional"))
    )
    (net (code "65") (name "VBAT") (class "Default")
      (node (ref "C19") (pin "1") (pinfunction "1_1") (pintype "passive"))
      (node (ref "D4") (pin "A") (pinfunction "A_A") (pintype "passive"))
      (node (ref "JP8") (pin "1") (pinfunction "1_1") (pintype "passive"))
      (node (ref "SJ10") (pin "2") (pinfunction "2_2") (pintype "passive"))
      (node (ref "X1") (pin "2") (pinfunction "2_2") (pintype "passive"))
    )
    (net (code "66") (name "VBUS") (class "Default")
      (node (ref "C16") (pin "1") (pinfunction "1_1") (pintype "passive"))
      (node (ref "CHG") (pin "A") (pinfunction "A_A") (pintype "passive"))
      (node (ref "D4") (pin "C") (pinfunction "C_C") (pintype "passive"))
      (node (ref "IC1") (pin "8") (pinfunction "VBUS_8") (pintype "power_in"))
      (node (ref "JP8") (pin "3") (pinfunction "3_3") (pintype "passive"))
      (node (ref "R28") (pin "2") (pinfunction "2_2") (pintype "passive"))
      (node (ref "U4") (pin "1") (pinfunction "IN_1") (pintype "power_in"))
      (node (ref "U5") (pin "4") (pinfunction "VDD_4") (pintype "power_in"))
      (node (ref "X4") (pin "VBUS") (pinfunction "VBUS_VBUS") (pintype "power_in"))
    )
    (net (code "67") (name "VDD") (class "Default")
      (node (ref "C10") (pin "1") (pinfunction "1_1") (pintype "passive"))
      (node (ref "C11") (pin "1") (pinfunction "1_1") (pintype "passive"))
      (node (ref "C12") (pin "1") (pinfunction "1_1") (pintype "passive"))
      (node (ref "C15") (pin "1") (pinfunction "1_1") (pintype "passive"))
      (node (ref "C2") (pin "1") (pinfunction "1_1") (pintype "passive"))
      (node (ref "C3") (pin "1") (pinfunction "1_1") (pintype "passive"))
      (node (ref "C4") (pin "1") (pinfunction "1_1") (pintype "passive"))
      (node (ref "C6") (pin "1") (pinfunction "1_1") (pintype "passive"))
      (node (ref "C7") (pin "1") (pinfunction "1_1") (pintype "passive"))
      (node (ref "JP1") (pin "2") (pinfunction "2_2") (pintype "passive"))
      (node (ref "JP3") (pin "2") (pinfunction "2_2") (pintype "passive"))
      (node (ref "JP5") (pin "2") (pinfunction "2_2") (pintype "passive"))
      (node (ref "SJ1") (pin "2") (pinfunction "2_2") (pintype "passive"))
      (node (ref "SJ2") (pin "2") (pinfunction "2_2") (pintype "passive"))
      (node (ref "SJ3") (pin "2") (pinfunction "2_2") (pintype "passive"))
      (node (ref "SJ4") (pin "2") (pinfunction "2_2") (pintype "passive"))
      (node (ref "SJ5") (pin "2") (pinfunction "2_2") (pintype "passive"))
      (node (ref "SJ6") (pin "2") (pinfunction "2_2") (pintype "passive"))
      (node (ref "SJ7") (pin "2") (pinfunction "2_2") (pintype "passive"))
      (node (ref "SJ8") (pin "2") (pinfunction "2_2") (pintype "passive"))
      (node (ref "SJ9") (pin "2") (pinfunction "2_2") (pintype "passive"))
      (node (ref "U1") (pin "1") (pinfunction "VDDIO_1") (pintype "bidirectional"))
      (node (ref "U1") (pin "22") (pinfunction "VDD_22") (pintype "bidirectional"))
      (node (ref "U1") (pin "23") (pinfunction "VDD_23") (pintype "bidirectional"))
      (node (ref "U1") (pin "3") (pinfunction "VDDIO_3") (pintype "bidirectional"))
      (node (ref "U2") (pin "1") (pinfunction "VDDIO_1") (pintype "bidirectional"))
      (node (ref "U2") (pin "22") (pinfunction "VDD_22") (pintype "bidirectional"))
      (node (ref "U2") (pin "23") (pinfunction "VDD_23") (pintype "bidirectional"))
      (node (ref "U2") (pin "3") (pinfunction "VDDIO_3") (pintype "bidirectional"))
      (node (ref "U3") (pin "1") (pinfunction "VDDIO_1") (pintype "bidirectional"))
      (node (ref "U3") (pin "22") (pinfunction "VDD_22") (pintype "bidirectional"))
      (node (ref "U3") (pin "23") (pinfunction "VDD_23") (pintype "bidirectional"))
      (node (ref "U3") (pin "3") (pinfunction "VDDIO_3") (pintype "bidirectional"))
    )
    (net (code "68") (name "unconnected-(IC1A-#RST-Pad9)") (class "Default")
      (node (ref "IC1") (pin "9") (pinfunction "#RST_9") (pintype "bidirectional"))
    )
    (net (code "69") (name "unconnected-(IC1A-#SUSPEND-Pad15)") (class "Default")
      (node (ref "IC1") (pin "15") (pinfunction "#SUSPEND_15") (pintype "output"))
    )
    (net (code "70") (name "unconnected-(IC1A-CTS-Pad18)") (class "Default")
      (node (ref "IC1") (pin "18") (pinfunction "CTS_18") (pintype "input"))
    )
    (net (code "71") (name "unconnected-(IC1A-DCD-Pad24)") (class "Default")
      (node (ref "IC1") (pin "24") (pinfunction "DCD_24") (pintype "input"))
    )
    (net (code "72") (name "unconnected-(IC1A-DSR-Pad22)") (class "Default")
      (node (ref "IC1") (pin "22") (pinfunction "DSR_22") (pintype "input"))
    )
    (net (code "73") (name "unconnected-(IC1A-GPIO0{slash}TXLED-Pad14)") (class "Default")
      (node (ref "IC1") (pin "14") (pinfunction "GPIO0/TXLED_14") (pintype "bidirectional"))
    )
    (net (code "74") (name "unconnected-(IC1A-GPIO1{slash}RXLED-Pad13)") (class "Default")
      (node (ref "IC1") (pin "13") (pinfunction "GPIO1/RXLED_13") (pintype "bidirectional"))
    )
    (net (code "75") (name "unconnected-(IC1A-GPIO2-Pad12)") (class "Default")
      (node (ref "IC1") (pin "12") (pinfunction "GPIO2_12") (pintype "bidirectional"))
    )
    (net (code "76") (name "unconnected-(IC1A-GPIO3-Pad11)") (class "Default")
      (node (ref "IC1") (pin "11") (pinfunction "GPIO3_11") (pintype "bidirectional"))
    )
    (net (code "77") (name "unconnected-(IC1A-NC-Pad10)") (class "Default")
      (node (ref "IC1") (pin "10") (pinfunction "NC_10") (pintype "no_connect"))
    )
    (net (code "78") (name "unconnected-(IC1A-RI-Pad1)") (class "Default")
      (node (ref "IC1") (pin "1") (pinfunction "RI_1") (pintype "input"))
    )
    (net (code "79") (name "unconnected-(IC1A-SUSPEND-Pad17)") (class "Default")
      (node (ref "IC1") (pin "17") (pinfunction "SUSPEND_17") (pintype "output"))
    )
    (net (code "80") (name "unconnected-(IC1A-VPP-Pad16)") (class "Default")
      (node (ref "IC1") (pin "16") (pinfunction "VPP_16") (pintype "bidirectional"))
    )
    (net (code "81") (name "unconnected-(JP7-Pad7)") (class "Default")
      (node (ref "JP7") (pin "7") (pinfunction "7_7") (pintype "passive"))
    )
    (net (code "82") (name "unconnected-(JP7-Pad8)") (class "Default")
      (node (ref "JP7") (pin "8") (pinfunction "8_8") (pintype "passive"))
    )
    (net (code "83") (name "unconnected-(JP7-Pad9)") (class "Default")
      (node (ref "JP7") (pin "9") (pinfunction "9_9") (pintype "passive"))
    )
    (net (code "84") (name "unconnected-(JP7-Pad10)") (class "Default")
      (node (ref "JP7") (pin "10") (pinfunction "10_10") (pintype "passive"))
    )
    (net (code "85") (name "unconnected-(JP7-Pad11)") (class "Default")
      (node (ref "JP7") (pin "11") (pinfunction "11_11") (pintype "passive"))
    )
    (net (code "86") (name "unconnected-(JP7-Pad14)") (class "Default")
      (node (ref "JP7") (pin "14") (pinfunction "14_14") (pintype "passive"))
    )
    (net (code "87") (name "unconnected-(U4-P4-Pad4)") (class "Default")
      (node (ref "U4") (pin "4") (pinfunction "P4_4") (pintype "bidirectional"))
    )
    (net (code "88") (name "unconnected-(X2-CLK-Pad20)") (class "Default")
      (node (ref "X2") (pin "20") (pinfunction "CLK_20") (pintype "bidirectional"))
    )
    (net (code "89") (name "unconnected-(X2-CS-Pad17)") (class "Default")
      (node (ref "X2") (pin "17") (pinfunction "CS_17") (pintype "bidirectional"))
    )
    (net (code "90") (name "unconnected-(X2-DI-Pad21)") (class "Default")
      (node (ref "X2") (pin "21") (pinfunction "DI_21") (pintype "bidirectional"))
    )
    (net (code "91") (name "unconnected-(X2-DO-Pad18)") (class "Default")
      (node (ref "X2") (pin "18") (pinfunction "DO_18") (pintype "bidirectional"))
    )
    (net (code "92") (name "unconnected-(X2-GPIO9-Pad22)") (class "Default")
      (node (ref "X2") (pin "22") (pinfunction "GPIO9_22") (pintype "bidirectional"))
    )
    (net (code "93") (name "unconnected-(X2-GPIO10-Pad19)") (class "Default")
      (node (ref "X2") (pin "19") (pinfunction "GPIO10_19") (pintype "bidirectional"))
    )
    (net (code "94") (name "unconnected-(X4-PadID)") (class "Default")
      (node (ref "X4") (pin "ID") (pinfunction "ID_ID") (pintype "bidirectional"))
    )
  )
)
